# battery_monitor_v2_0.net
KiCad netlist of a schematic drawn in Altium Designer
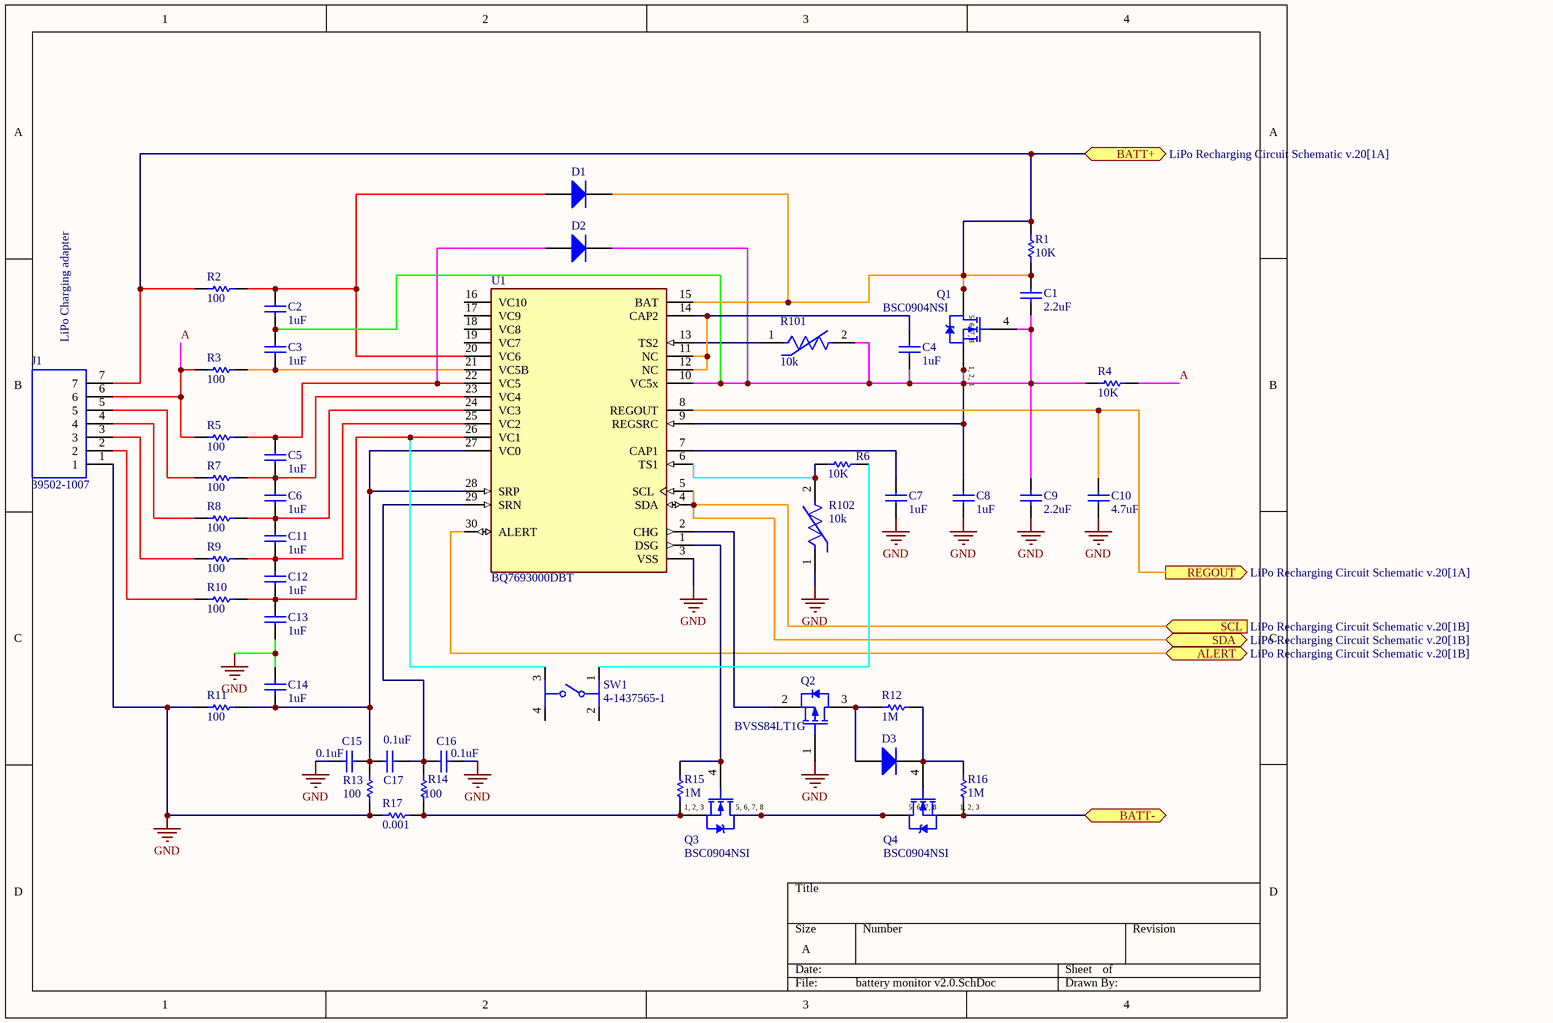
[diagram p0: battery monitor v2.0.SchDoc]

(export (version "E")
  (design (tool "Eeschema 10.0.6"))
  (components
    (comp (ref "C1")
      (value "2.2uF")
      (footprint "CAPC2012X145N:CAPC2012X145N")
      (description "Capacitor")
      (libsource (lib "Simulation Generic Components") (part "Capacitor"))
    )
    (comp (ref "C2")
      (value "1uF")
      (footprint "CAPC2012X145N:CAPC2012X145N")
      (description "Capacitor")
      (libsource (lib "Simulation Generic Components") (part "Capacitor"))
    )
    (comp (ref "C3")
      (value "1uF")
      (footprint "CAPC2012X145N:CAPC2012X145N")
      (description "Capacitor")
      (libsource (lib "Simulation Generic Components") (part "Capacitor"))
    )
    (comp (ref "C4")
      (value "1uF")
      (footprint "CAPC2012X145N:CAPC2012X145N")
      (description "Capacitor")
      (libsource (lib "Simulation Generic Components") (part "Capacitor"))
    )
    (comp (ref "C5")
      (value "1uF")
      (footprint "CAPC2012X145N:CAPC2012X145N")
      (description "Capacitor")
      (libsource (lib "Simulation Generic Components") (part "Capacitor"))
    )
    (comp (ref "C6")
      (value "1uF")
      (footprint "CAPC2012X145N:CAPC2012X145N")
      (description "Capacitor")
      (libsource (lib "Simulation Generic Components") (part "Capacitor"))
    )
    (comp (ref "C7")
      (value "1uF")
      (footprint "CAPC2012X145N:CAPC2012X145N")
      (description "Capacitor")
      (libsource (lib "Simulation Generic Components") (part "Capacitor"))
    )
    (comp (ref "C8")
      (value "1uF")
      (footprint "CAPC2012X145N:CAPC2012X145N")
      (description "Capacitor")
      (libsource (lib "Simulation Generic Components") (part "Capacitor"))
    )
    (comp (ref "C9")
      (value "2.2uF")
      (footprint "CAPC2012X145N:CAPC2012X145N")
      (description "Capacitor")
      (libsource (lib "Simulation Generic Components") (part "Capacitor"))
    )
    (comp (ref "C10")
      (value "4.7uF")
      (footprint "CAPC2012X145N:CAPC2012X145N")
      (description "Capacitor")
      (libsource (lib "Simulation Generic Components") (part "Capacitor"))
    )
    (comp (ref "C11")
      (value "1uF")
      (footprint "CAPC2012X145N:CAPC2012X145N")
      (description "Capacitor")
      (libsource (lib "Simulation Generic Components") (part "Capacitor"))
    )
    (comp (ref "C12")
      (value "1uF")
      (footprint "CAPC2012X145N:CAPC2012X145N")
      (description "Capacitor")
      (libsource (lib "Simulation Generic Components") (part "Capacitor"))
    )
    (comp (ref "C13")
      (value "1uF")
      (footprint "CAPC2012X145N:CAPC2012X145N")
      (description "Capacitor")
      (libsource (lib "Simulation Generic Components") (part "Capacitor"))
    )
    (comp (ref "C14")
      (value "1uF")
      (footprint "CAPC2012X145N:CAPC2012X145N")
      (description "Capacitor")
      (libsource (lib "Simulation Generic Components") (part "Capacitor"))
    )
    (comp (ref "C15")
      (value "0.1uF")
      (footprint "CAPC2012X145N:CAPC2012X145N")
      (description "Capacitor")
      (libsource (lib "Simulation Generic Components") (part "Capacitor"))
    )
    (comp (ref "C16")
      (value "0.1uF")
      (footprint "CAPC2012X145N:CAPC2012X145N")
      (description "Capacitor")
      (libsource (lib "Simulation Generic Components") (part "Capacitor"))
    )
    (comp (ref "C17")
      (value "0.1uF")
      (footprint "CAPC2012X145N:CAPC2012X145N")
      (description "Capacitor")
      (libsource (lib "Simulation Generic Components") (part "Capacitor"))
    )
    (comp (ref "D1")
      (value "1N4001-T")
      (footprint "DIOD-DO-41-P-2_V")
      (description "1.0 A Rectifier, 15 pF, 50 V, -65 to 150 degC, 2-Pin DO-41 Plastic, RoHS, Tape and Reel")
      (fields (field (name "MANUFACTURER") "Diodes Inc"))
      (libsource (lib "Altium Content Vault") (part "DIOD-D-A1K2-2"))
    )
    (comp (ref "D2")
      (value "1N4001-T")
      (footprint "DIOD-DO-41-P-2_V")
      (description "1.0 A Rectifier, 15 pF, 50 V, -65 to 150 degC, 2-Pin DO-41 Plastic, RoHS, Tape and Reel")
      (fields (field (name "MANUFACTURER") "Diodes Inc"))
      (libsource (lib "Altium Content Vault") (part "DIOD-D-A1K2-2"))
    )
    (comp (ref "D3")
      (value "1N4001-T")
      (footprint "DIOD-DO-41-P-2_V")
      (description "1.0 A Rectifier, 15 pF, 50 V, -65 to 150 degC, 2-Pin DO-41 Plastic, RoHS, Tape and Reel")
      (fields (field (name "MANUFACTURER") "Diodes Inc"))
      (libsource (lib "Altium Content Vault") (part "DIOD-D-A1K2-2"))
    )
    (comp (ref "J1")
      (value "39502-1007")
      (footprint "SHDRRA7W80P0X350_1X7_2590X920X730P")
      (description "Pluggable Terminal Blocks 3.5MM HOR PCB HDR 7 CIRCUITS")
      (fields (field (name "MOUSER PART NUMBER") "538-39502-1007"))
      (libsource (lib "39502-1007") (part "39502-1007"))
    )
    (comp (ref "Q1")
      (value "BSC0904NSI")
      (footprint "INF-PG-TDSON-8-1_V")
      (description "N-Channel OptiMOS Power-MOSFET, 30 V VDS, 78 A ID, -55 to 150 degC, PG-TDSON-8-1, Reel, Green")
      (fields (field (name "MANUFACTURER") "Infineon"))
      (libsource (lib "Altium Content Vault") (part "INF-NEMOS-SSSGDDDD-8-B"))
    )
    (comp (ref "Q2")
      (value "BVSS84LT1G")
      (footprint "ONSC-SOT-23-3-318-08_V")
      (description "Power MOSFET Single P-Channel, -50 V, 10 Ohm, 3-Pin SOT-23, Pb-Free, Tape and Reel")
      (fields (field (name "MANUFACTURER") "On Semiconductor"))
      (libsource (lib "Altium Content Vault") (part "ONSC-PMOS-G1S2D3-3_D"))
    )
    (comp (ref "Q3")
      (value "BSC0904NSI")
      (footprint "INF-PG-TDSON-8-1_V")
      (description "N-Channel OptiMOS Power-MOSFET, 30 V VDS, 78 A ID, -55 to 150 degC, PG-TDSON-8-1, Reel, Green")
      (fields (field (name "MANUFACTURER") "Infineon"))
      (libsource (lib "Altium Content Vault") (part "INF-NEMOS-SSSGDDDD-8-B"))
    )
    (comp (ref "Q4")
      (value "BSC0904NSI")
      (footprint "INF-PG-TDSON-8-1_V")
      (description "N-Channel OptiMOS Power-MOSFET, 30 V VDS, 78 A ID, -55 to 150 degC, PG-TDSON-8-1, Reel, Green")
      (fields (field (name "MANUFACTURER") "Infineon"))
      (libsource (lib "Altium Content Vault") (part "INF-NEMOS-SSSGDDDD-8-B"))
    )
    (comp (ref "R1")
      (value "10K")
      (footprint "CAPC2012X145N:CAPC2012X145N")
      (description "Resistor")
      (libsource (lib "Simulation Generic Components") (part "Resistor"))
    )
    (comp (ref "R2")
      (value "100")
      (footprint "CAPC2012X145N:CAPC2012X145N")
      (description "Resistor")
      (libsource (lib "Simulation Generic Components") (part "Resistor"))
    )
    (comp (ref "R3")
      (value "100")
      (footprint "CAPC2012X145N:CAPC2012X145N")
      (description "Resistor")
      (libsource (lib "Simulation Generic Components") (part "Resistor"))
    )
    (comp (ref "R4")
      (value "10K")
      (footprint "CAPC2012X145N:CAPC2012X145N")
      (description "Resistor")
      (libsource (lib "Simulation Generic Components") (part "Resistor"))
    )
    (comp (ref "R5")
      (value "100")
      (footprint "CAPC2012X145N:CAPC2012X145N")
      (description "Resistor")
      (libsource (lib "Simulation Generic Components") (part "Resistor"))
    )
    (comp (ref "R6")
      (value "10K")
      (footprint "CAPC2012X145N:CAPC2012X145N")
      (description "Resistor")
      (libsource (lib "Simulation Generic Components") (part "Resistor"))
    )
    (comp (ref "R7")
      (value "100")
      (footprint "CAPC2012X145N:CAPC2012X145N")
      (description "Resistor")
      (libsource (lib "Simulation Generic Components") (part "Resistor"))
    )
    (comp (ref "R8")
      (value "100")
      (footprint "CAPC2012X145N:CAPC2012X145N")
      (description "Resistor")
      (libsource (lib "Simulation Generic Components") (part "Resistor"))
    )
    (comp (ref "R9")
      (value "100")
      (footprint "CAPC2012X145N:CAPC2012X145N")
      (description "Resistor")
      (libsource (lib "Simulation Generic Components") (part "Resistor"))
    )
    (comp (ref "R10")
      (value "100")
      (footprint "CAPC2012X145N:CAPC2012X145N")
      (description "Resistor")
      (libsource (lib "Simulation Generic Components") (part "Resistor"))
    )
    (comp (ref "R11")
      (value "100")
      (footprint "CAPC2012X145N:CAPC2012X145N")
      (description "Resistor")
      (libsource (lib "Simulation Generic Components") (part "Resistor"))
    )
    (comp (ref "R12")
      (value "1M")
      (footprint "CAPC2012X145N:CAPC2012X145N")
      (description "Resistor")
      (libsource (lib "Simulation Generic Components") (part "Resistor"))
    )
    (comp (ref "R13")
      (value "100")
      (footprint "CAPC2012X145N:CAPC2012X145N")
      (description "Resistor")
      (libsource (lib "Simulation Generic Components") (part "Resistor"))
    )
    (comp (ref "R14")
      (value "100")
      (footprint "CAPC2012X145N:CAPC2012X145N")
      (description "Resistor")
      (libsource (lib "Simulation Generic Components") (part "Resistor"))
    )
    (comp (ref "R15")
      (value "1M")
      (footprint "CAPC2012X145N:CAPC2012X145N")
      (description "Resistor")
      (libsource (lib "Simulation Generic Components") (part "Resistor"))
    )
    (comp (ref "R16")
      (value "1M")
      (footprint "CAPC2012X145N:CAPC2012X145N")
      (description "Resistor")
      (libsource (lib "Simulation Generic Components") (part "Resistor"))
    )
    (comp (ref "R17")
      (value "0.001")
      (footprint "CAPC2012X145N:CAPC2012X145N")
      (description "Resistor")
      (libsource (lib "Simulation Generic Components") (part "Resistor"))
    )
    (comp (ref "R101")
      (value "10k")
      (footprint "FP-NCU18-0_15-IPC_B")
      (description "THERMISTOR NTC")
      (libsource (lib "Altium Content Vault") (part "3b148a6ebabc5fb4d708a66c052d352"))
    )
    (comp (ref "R102")
      (value "10k")
      (footprint "FP-NCU18-0_15-IPC_B")
      (description "THERMISTOR NTC")
      (libsource (lib "Altium Content Vault") (part "3b148a6ebabc5fb4d708a66c052d352"))
    )
    (comp (ref "SW1")
      (value "4-1437565-1")
      (footprint "FP-4-1437565-1-MFG")
      (description "SWITCH TACTILE SPST-NO 0.05A 24V")
      (fields
        (field (name "MANUFACTURER") "TE Connectivity")
        (field (name "OCTOPART") "https://octopart.com/fsm4jsma-te+connectivity-55488004")
      )
      (libsource (lib "Altium Content Vault") (part "b8895f3f4cefb76e1819d2863dba89b"))
    )
    (comp (ref "U1")
      (value "BQ7693000DBT")
      (footprint "FP-DBT0030A-IPC_A")
      (description "IC BATT MGMT LI-ION AFE 30TSSOP")
      (libsource (lib "Altium Content Vault") (part "7900404cda58c98bebdb682fa71012e"))
    )
  )
  (nets
    (net (code "1") (name "/A") (class "Default")
      (node (ref "J1") (pin "6") (pinfunction "6_6") (pintype "passive"))
      (node (ref "R3") (pin "2") (pinfunction "2_2") (pintype "passive"))
      (node (ref "R4") (pin "1") (pinfunction "1_1") (pintype "passive"))
      (node (ref "R5") (pin "2") (pinfunction "2_2") (pintype "passive"))
    )
    (net (code "2") (name "/ALERT") (class "Default")
      (node (ref "U1") (pin "30") (pinfunction "ALERT_30") (pintype "bidirectional"))
    )
    (net (code "3") (name "/BATT+") (class "Default")
      (node (ref "C1") (pin "2") (pinfunction "2_2") (pintype "passive"))
      (node (ref "D1") (pin "2") (pinfunction "K_2") (pintype "passive"))
      (node (ref "J1") (pin "7") (pinfunction "7_7") (pintype "passive"))
      (node (ref "Q1") (pin "5") (pinfunction "DRAIN_5") (pintype "passive"))
      (node (ref "Q1") (pin "6") (pinfunction "DRAIN_6") (pintype "passive"))
      (node (ref "Q1") (pin "7") (pinfunction "DRAIN_7") (pintype "passive"))
      (node (ref "Q1") (pin "8") (pinfunction "DRAIN_8") (pintype "passive"))
      (node (ref "R1") (pin "1") (pinfunction "1_1") (pintype "passive"))
      (node (ref "R1") (pin "2") (pinfunction "2_2") (pintype "passive"))
      (node (ref "R2") (pin "2") (pinfunction "2_2") (pintype "passive"))
      (node (ref "U1") (pin "15") (pinfunction "BAT_15") (pintype "power_in"))
    )
    (net (code "4") (name "/BATT-") (class "Default")
      (node (ref "Q4") (pin "1") (pinfunction "SOURCE_1") (pintype "passive"))
      (node (ref "Q4") (pin "2") (pinfunction "SOURCE_2") (pintype "passive"))
      (node (ref "Q4") (pin "3") (pinfunction "SOURCE_3") (pintype "passive"))
      (node (ref "R16") (pin "1") (pinfunction "1_1") (pintype "passive"))
    )
    (net (code "5") (name "/REGOUT") (class "Default")
      (node (ref "C10") (pin "2") (pinfunction "2_2") (pintype "passive"))
      (node (ref "U1") (pin "8") (pinfunction "REGOUT_8") (pintype "power_in"))
    )
    (net (code "6") (name "/SCL") (class "Default")
      (node (ref "U1") (pin "4") (pinfunction "SDA_4") (pintype "bidirectional"))
      (node (ref "U1") (pin "5") (pinfunction "SCL_5") (pintype "input"))
    )
    (net (code "7") (name "GND") (class "Default")
      (node (ref "C10") (pin "1") (pinfunction "1_1") (pintype "passive"))
      (node (ref "C13") (pin "1") (pinfunction "1_1") (pintype "passive"))
      (node (ref "C14") (pin "2") (pinfunction "2_2") (pintype "passive"))
      (node (ref "C15") (pin "2") (pinfunction "2_2") (pintype "passive"))
      (node (ref "C16") (pin "1") (pinfunction "1_1") (pintype "passive"))
      (node (ref "C7") (pin "1") (pinfunction "1_1") (pintype "passive"))
      (node (ref "C8") (pin "1") (pinfunction "1_1") (pintype "passive"))
      (node (ref "C9") (pin "1") (pinfunction "1_1") (pintype "passive"))
      (node (ref "J1") (pin "1") (pinfunction "1_1") (pintype "passive"))
      (node (ref "Q2") (pin "1") (pinfunction "G_1") (pintype "passive"))
      (node (ref "R102") (pin "1") (pinfunction "1_1") (pintype "passive"))
      (node (ref "R11") (pin "2") (pinfunction "2_2") (pintype "passive"))
      (node (ref "R13") (pin "2") (pinfunction "2_2") (pintype "passive"))
      (node (ref "R17") (pin "1") (pinfunction "1_1") (pintype "passive"))
      (node (ref "U1") (pin "3") (pinfunction "VSS_3") (pintype "power_in"))
    )
    (net (code "8") (name "Net-(D1-A)") (class "Default")
      (node (ref "C2") (pin "2") (pinfunction "2_2") (pintype "passive"))
      (node (ref "D1") (pin "1") (pinfunction "A_1") (pintype "passive"))
      (node (ref "R2") (pin "1") (pinfunction "1_1") (pintype "passive"))
      (node (ref "U1") (pin "20") (pinfunction "VC6_20") (pintype "power_in"))
    )
    (net (code "9") (name "Net-(D2-A)") (class "Default")
      (node (ref "C5") (pin "2") (pinfunction "2_2") (pintype "passive"))
      (node (ref "D2") (pin "1") (pinfunction "A_1") (pintype "passive"))
      (node (ref "R5") (pin "1") (pinfunction "1_1") (pintype "passive"))
      (node (ref "U1") (pin "22") (pinfunction "VC5_22") (pintype "power_in"))
    )
    (net (code "10") (name "Net-(D2-K)") (class "Default")
      (node (ref "C1") (pin "1") (pinfunction "1_1") (pintype "passive"))
      (node (ref "C2") (pin "1") (pinfunction "1_1") (pintype "passive"))
      (node (ref "C3") (pin "2") (pinfunction "2_2") (pintype "passive"))
      (node (ref "C4") (pin "1") (pinfunction "1_1") (pintype "passive"))
      (node (ref "C8") (pin "2") (pinfunction "2_2") (pintype "passive"))
      (node (ref "C9") (pin "2") (pinfunction "2_2") (pintype "passive"))
      (node (ref "D2") (pin "2") (pinfunction "K_2") (pintype "passive"))
      (node (ref "Q1") (pin "1") (pinfunction "SOURCE_1") (pintype "passive"))
      (node (ref "Q1") (pin "2") (pinfunction "SOURCE_2") (pintype "passive"))
      (node (ref "Q1") (pin "3") (pinfunction "SOURCE_3") (pintype "passive"))
      (node (ref "Q1") (pin "4") (pinfunction "GATE_4") (pintype "passive"))
      (node (ref "R101") (pin "2") (pinfunction "2_2") (pintype "passive"))
      (node (ref "R4") (pin "2") (pinfunction "2_2") (pintype "passive"))
      (node (ref "U1") (pin "10") (pinfunction "VC5x_10") (pintype "power_in"))
      (node (ref "U1") (pin "9") (pinfunction "REGSRC_9") (pintype "input"))
    )
    (net (code "11") (name "Net-(D3-A)") (class "Default")
      (node (ref "D3") (pin "1") (pinfunction "A_1") (pintype "passive"))
      (node (ref "Q2") (pin "3") (pinfunction "D_3") (pintype "passive"))
      (node (ref "R12") (pin "2") (pinfunction "2_2") (pintype "passive"))
    )
    (net (code "12") (name "Net-(D3-K)") (class "Default")
      (node (ref "D3") (pin "2") (pinfunction "K_2") (pintype "passive"))
      (node (ref "Q4") (pin "4") (pinfunction "GATE_4") (pintype "passive"))
      (node (ref "R12") (pin "1") (pinfunction "1_1") (pintype "passive"))
      (node (ref "R16") (pin "2") (pinfunction "2_2") (pintype "passive"))
    )
    (net (code "13") (name "Net-(J1-Pad2)") (class "Default")
      (node (ref "J1") (pin "2") (pinfunction "2_2") (pintype "passive"))
      (node (ref "R10") (pin "2") (pinfunction "2_2") (pintype "passive"))
    )
    (net (code "14") (name "Net-(J1-Pad3)") (class "Default")
      (node (ref "J1") (pin "3") (pinfunction "3_3") (pintype "passive"))
      (node (ref "R9") (pin "2") (pinfunction "2_2") (pintype "passive"))
    )
    (net (code "15") (name "Net-(J1-Pad4)") (class "Default")
      (node (ref "J1") (pin "4") (pinfunction "4_4") (pintype "passive"))
      (node (ref "R8") (pin "2") (pinfunction "2_2") (pintype "passive"))
    )
    (net (code "16") (name "Net-(J1-Pad5)") (class "Default")
      (node (ref "J1") (pin "5") (pinfunction "5_5") (pintype "passive"))
      (node (ref "R7") (pin "2") (pinfunction "2_2") (pintype "passive"))
    )
    (net (code "17") (name "Net-(Q2-S)") (class "Default")
      (node (ref "Q2") (pin "2") (pinfunction "S_2") (pintype "passive"))
      (node (ref "U1") (pin "2") (pinfunction "CHG_2") (pintype "output"))
    )
    (net (code "18") (name "Net-(Q3-DRAIN-Pad5)") (class "Default")
      (node (ref "Q3") (pin "5") (pinfunction "DRAIN_5") (pintype "passive"))
      (node (ref "Q3") (pin "6") (pinfunction "DRAIN_6") (pintype "passive"))
      (node (ref "Q3") (pin "7") (pinfunction "DRAIN_7") (pintype "passive"))
      (node (ref "Q3") (pin "8") (pinfunction "DRAIN_8") (pintype "passive"))
      (node (ref "Q4") (pin "5") (pinfunction "DRAIN_5") (pintype "passive"))
      (node (ref "Q4") (pin "6") (pinfunction "DRAIN_6") (pintype "passive"))
      (node (ref "Q4") (pin "7") (pinfunction "DRAIN_7") (pintype "passive"))
      (node (ref "Q4") (pin "8") (pinfunction "DRAIN_8") (pintype "passive"))
    )
    (net (code "19") (name "Net-(Q3-GATE)") (class "Default")
      (node (ref "Q3") (pin "4") (pinfunction "GATE_4") (pintype "passive"))
      (node (ref "R15") (pin "2") (pinfunction "2_2") (pintype "passive"))
      (node (ref "U1") (pin "1") (pinfunction "DSG_1") (pintype "output"))
    )
    (net (code "20") (name "Net-(Q3-SOURCE-Pad1)") (class "Default")
      (node (ref "Q3") (pin "1") (pinfunction "SOURCE_1") (pintype "passive"))
      (node (ref "Q3") (pin "2") (pinfunction "SOURCE_2") (pintype "passive"))
      (node (ref "Q3") (pin "3") (pinfunction "SOURCE_3") (pintype "passive"))
      (node (ref "R14") (pin "2") (pinfunction "2_2") (pintype "passive"))
      (node (ref "R15") (pin "1") (pinfunction "1_1") (pintype "passive"))
      (node (ref "R17") (pin "2") (pinfunction "2_2") (pintype "passive"))
    )
    (net (code "21") (name "Net-(R6-Pad1)") (class "Default")
      (node (ref "R6") (pin "1") (pinfunction "1_1") (pintype "passive"))
      (node (ref "SW1") (pin "1") (pinfunction "1_1") (pintype "passive"))
    )
    (net (code "22") (name "Net-(U1-CAP1)") (class "Default")
      (node (ref "C7") (pin "2") (pinfunction "2_2") (pintype "passive"))
      (node (ref "U1") (pin "7") (pinfunction "CAP1_7") (pintype "passive"))
    )
    (net (code "23") (name "Net-(U1-CAP2)") (class "Default")
      (node (ref "C4") (pin "2") (pinfunction "2_2") (pintype "passive"))
      (node (ref "U1") (pin "11") (pinfunction "NC_11") (pintype "passive"))
      (node (ref "U1") (pin "12") (pinfunction "NC_12") (pintype "passive"))
      (node (ref "U1") (pin "14") (pinfunction "CAP2_14") (pintype "passive"))
    )
    (net (code "24") (name "Net-(U1-SRN)") (class "Default")
      (node (ref "C16") (pin "2") (pinfunction "2_2") (pintype "passive"))
      (node (ref "C17") (pin "1") (pinfunction "1_1") (pintype "passive"))
      (node (ref "R14") (pin "1") (pinfunction "1_1") (pintype "passive"))
      (node (ref "U1") (pin "29") (pinfunction "SRN_29") (pintype "input"))
    )
    (net (code "25") (name "Net-(U1-SRP)") (class "Default")
      (node (ref "C14") (pin "1") (pinfunction "1_1") (pintype "passive"))
      (node (ref "C15") (pin "1") (pinfunction "1_1") (pintype "passive"))
      (node (ref "C17") (pin "2") (pinfunction "2_2") (pintype "passive"))
      (node (ref "R11") (pin "1") (pinfunction "1_1") (pintype "passive"))
      (node (ref "R13") (pin "1") (pinfunction "1_1") (pintype "passive"))
      (node (ref "U1") (pin "27") (pinfunction "VC0_27") (pintype "power_in"))
      (node (ref "U1") (pin "28") (pinfunction "SRP_28") (pintype "input"))
    )
    (net (code "26") (name "Net-(U1-TS1)") (class "Default")
      (node (ref "R102") (pin "2") (pinfunction "2_2") (pintype "passive"))
      (node (ref "R6") (pin "2") (pinfunction "2_2") (pintype "passive"))
      (node (ref "U1") (pin "6") (pinfunction "TS1_6") (pintype "input"))
    )
    (net (code "27") (name "Net-(U1-TS2)") (class "Default")
      (node (ref "R101") (pin "1") (pinfunction "1_1") (pintype "passive"))
      (node (ref "U1") (pin "13") (pinfunction "TS2_13") (pintype "input"))
    )
    (net (code "28") (name "Net-(U1-VC1)") (class "Default")
      (node (ref "C12") (pin "1") (pinfunction "1_1") (pintype "passive"))
      (node (ref "C13") (pin "2") (pinfunction "2_2") (pintype "passive"))
      (node (ref "R10") (pin "1") (pinfunction "1_1") (pintype "passive"))
      (node (ref "SW1") (pin "3") (pinfunction "3_3") (pintype "passive"))
      (node (ref "U1") (pin "26") (pinfunction "VC1_26") (pintype "power_in"))
    )
    (net (code "29") (name "Net-(U1-VC2)") (class "Default")
      (node (ref "C11") (pin "1") (pinfunction "1_1") (pintype "passive"))
      (node (ref "C12") (pin "2") (pinfunction "2_2") (pintype "passive"))
      (node (ref "R9") (pin "1") (pinfunction "1_1") (pintype "passive"))
      (node (ref "U1") (pin "25") (pinfunction "VC2_25") (pintype "power_in"))
    )
    (net (code "30") (name "Net-(U1-VC3)") (class "Default")
      (node (ref "C11") (pin "2") (pinfunction "2_2") (pintype "passive"))
      (node (ref "C6") (pin "1") (pinfunction "1_1") (pintype "passive"))
      (node (ref "R8") (pin "1") (pinfunction "1_1") (pintype "passive"))
      (node (ref "U1") (pin "24") (pinfunction "VC3_24") (pintype "power_in"))
    )
    (net (code "31") (name "Net-(U1-VC4)") (class "Default")
      (node (ref "C5") (pin "1") (pinfunction "1_1") (pintype "passive"))
      (node (ref "C6") (pin "2") (pinfunction "2_2") (pintype "passive"))
      (node (ref "R7") (pin "1") (pinfunction "1_1") (pintype "passive"))
      (node (ref "U1") (pin "23") (pinfunction "VC4_23") (pintype "power_in"))
    )
    (net (code "32") (name "Net-(U1-VC5B)") (class "Default")
      (node (ref "C3") (pin "1") (pinfunction "1_1") (pintype "passive"))
      (node (ref "R3") (pin "1") (pinfunction "1_1") (pintype "passive"))
      (node (ref "U1") (pin "21") (pinfunction "VC5B_21") (pintype "power_in"))
    )
    (net (code "33") (name "unconnected-(SW1-Pad2)") (class "Default")
      (node (ref "SW1") (pin "2") (pinfunction "2_2") (pintype "passive"))
    )
    (net (code "34") (name "unconnected-(SW1-Pad4)") (class "Default")
      (node (ref "SW1") (pin "4") (pinfunction "4_4") (pintype "passive"))
    )
    (net (code "35") (name "unconnected-(U1-VC7-Pad19)") (class "Default")
      (node (ref "U1") (pin "19") (pinfunction "VC7_19") (pintype "power_in"))
    )
    (net (code "36") (name "unconnected-(U1-VC8-Pad18)") (class "Default")
      (node (ref "U1") (pin "18") (pinfunction "VC8_18") (pintype "power_in"))
    )
    (net (code "37") (name "unconnected-(U1-VC9-Pad17)") (class "Default")
      (node (ref "U1") (pin "17") (pinfunction "VC9_17") (pintype "power_in"))
    )
    (net (code "38") (name "unconnected-(U1-VC10-Pad16)") (class "Default")
      (node (ref "U1") (pin "16") (pinfunction "VC10_16") (pintype "power_in"))
    )
  )
)
